# Adafruit_ATECC608.net
KiCad netlist of a schematic drawn in EAGLE
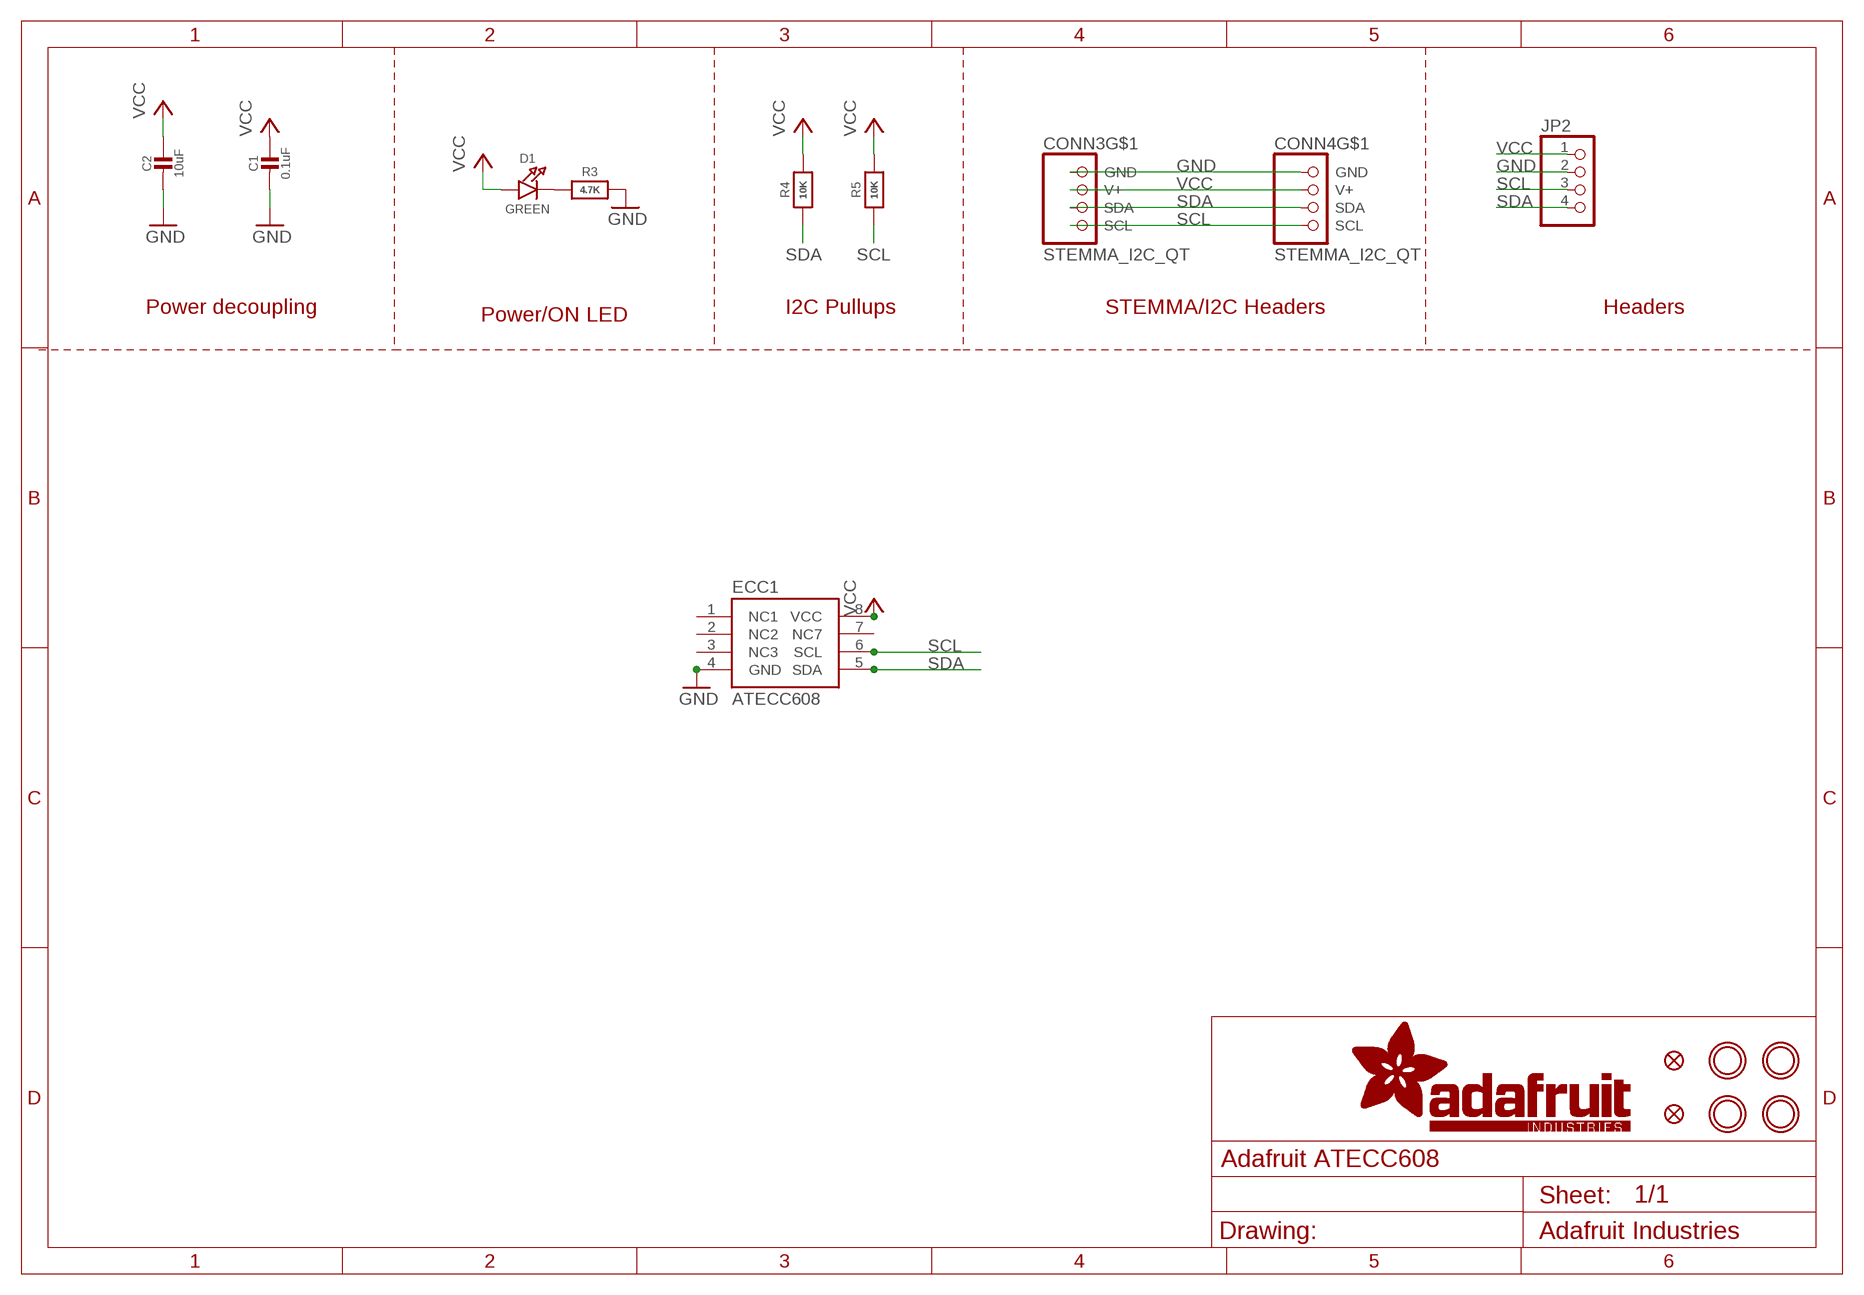
[diagram p0: schematic, sheet 1]

(export (version "E")
  (design (tool "Eeschema 10.0.6"))
  (components
    (comp (ref "C1")
      (value "0.1uF")
      (footprint "eagle-import:0603-NO")
      (libsource (lib "eagle-import") (part "CAP_CERAMIC0603_NO"))
    )
    (comp (ref "C2")
      (value "10uF")
      (footprint "eagle-import:0805-NO")
      (libsource (lib "eagle-import") (part "CAP_CERAMIC0805-NOOUTLINE"))
    )
    (comp (ref "CONN3")
      (value "STEMMA_I2C_QT")
      (footprint "eagle-import:JST_SH4")
      (libsource (lib "eagle-import") (part "STEMMA_I2C_QT"))
    )
    (comp (ref "CONN4")
      (value "STEMMA_I2C_QT")
      (footprint "eagle-import:JST_SH4")
      (libsource (lib "eagle-import") (part "STEMMA_I2C_QT"))
    )
    (comp (ref "D1")
      (value "GREEN")
      (footprint "eagle-import:CHIPLED_0603_NOOUTLINE")
      (libsource (lib "eagle-import") (part "LED0603_NOOUTLINE"))
    )
    (comp (ref "ECC1")
      (value "ATECC608")
      (footprint "eagle-import:SOIC8")
      (libsource (lib "eagle-import") (part "ATECC108"))
    )
    (comp (ref "FID3")
      (value "FIDUCIAL_1MM")
      (footprint "eagle-import:FIDUCIAL_1MM")
      (libsource (lib "eagle-import") (part "FIDUCIAL_1MM"))
    )
    (comp (ref "FID4")
      (value "FIDUCIAL_1MM")
      (footprint "eagle-import:FIDUCIAL_1MM")
      (libsource (lib "eagle-import") (part "FIDUCIAL_1MM"))
    )
    (comp (ref "JP2")
      (value "HEADER-1X4ROUND")
      (footprint "eagle-import:1X04_ROUND")
      (libsource (lib "eagle-import") (part "HEADER-1X4ROUND"))
    )
    (comp (ref "R3")
      (value "4.7K")
      (footprint "eagle-import:0603-NO")
      (libsource (lib "eagle-import") (part "RESISTOR_0603_NOOUT"))
    )
    (comp (ref "R4")
      (value "10K")
      (footprint "eagle-import:0603-NO")
      (libsource (lib "eagle-import") (part "RESISTOR_0603_NOOUT"))
    )
    (comp (ref "R5")
      (value "10K")
      (footprint "eagle-import:0603-NO")
      (libsource (lib "eagle-import") (part "RESISTOR_0603_NOOUT"))
    )
    (comp (ref "U$11")
      (value "MOUNTINGHOLE2.5")
      (footprint "eagle-import:MOUNTINGHOLE_2.5_PLATED")
      (libsource (lib "eagle-import") (part "MOUNTINGHOLE2.5"))
    )
    (comp (ref "U$12")
      (value "MOUNTINGHOLE2.5")
      (footprint "eagle-import:MOUNTINGHOLE_2.5_PLATED")
      (libsource (lib "eagle-import") (part "MOUNTINGHOLE2.5"))
    )
    (comp (ref "U$14")
      (value "MOUNTINGHOLE2.5")
      (footprint "eagle-import:MOUNTINGHOLE_2.5_PLATED")
      (libsource (lib "eagle-import") (part "MOUNTINGHOLE2.5"))
    )
    (comp (ref "U$15")
      (value "MOUNTINGHOLE2.5")
      (footprint "eagle-import:MOUNTINGHOLE_2.5_PLATED")
      (libsource (lib "eagle-import") (part "MOUNTINGHOLE2.5"))
    )
  )
  (nets
    (net (code "1") (name "/SCL") (class "Default")
      (node (ref "CONN3") (pin "4") (pinfunction "SCL_4") (pintype "passive"))
      (node (ref "CONN4") (pin "4") (pinfunction "SCL_4") (pintype "passive"))
      (node (ref "ECC1") (pin "6") (pinfunction "SCL_6") (pintype "bidirectional"))
      (node (ref "JP2") (pin "3") (pinfunction "3_3") (pintype "passive"))
      (node (ref "R5") (pin "1") (pinfunction "1_1") (pintype "passive"))
    )
    (net (code "2") (name "/SDA") (class "Default")
      (node (ref "CONN3") (pin "3") (pinfunction "SDA_3") (pintype "passive"))
      (node (ref "CONN4") (pin "3") (pinfunction "SDA_3") (pintype "passive"))
      (node (ref "ECC1") (pin "5") (pinfunction "SDA_5") (pintype "bidirectional"))
      (node (ref "JP2") (pin "4") (pinfunction "4_4") (pintype "passive"))
      (node (ref "R4") (pin "1") (pinfunction "1_1") (pintype "passive"))
    )
    (net (code "3") (name "GND") (class "Default")
      (node (ref "C1") (pin "2") (pinfunction "2_2") (pintype "passive"))
      (node (ref "C2") (pin "2") (pinfunction "2_2") (pintype "passive"))
      (node (ref "CONN3") (pin "1") (pinfunction "GND_1") (pintype "passive"))
      (node (ref "CONN4") (pin "1") (pinfunction "GND_1") (pintype "passive"))
      (node (ref "ECC1") (pin "4") (pinfunction "GND_4") (pintype "power_in"))
      (node (ref "JP2") (pin "2") (pinfunction "2_2") (pintype "passive"))
      (node (ref "R3") (pin "2") (pinfunction "2_2") (pintype "passive"))
    )
    (net (code "4") (name "Net-(D1-PadC)") (class "Default")
      (node (ref "D1") (pin "C") (pinfunction "C_C") (pintype "passive"))
      (node (ref "R3") (pin "1") (pinfunction "1_1") (pintype "passive"))
    )
    (net (code "5") (name "VCC") (class "Default")
      (node (ref "C1") (pin "1") (pinfunction "1_1") (pintype "passive"))
      (node (ref "C2") (pin "1") (pinfunction "1_1") (pintype "passive"))
      (node (ref "CONN3") (pin "2") (pinfunction "V+_2") (pintype "passive"))
      (node (ref "CONN4") (pin "2") (pinfunction "V+_2") (pintype "passive"))
      (node (ref "D1") (pin "A") (pinfunction "A_A") (pintype "passive"))
      (node (ref "ECC1") (pin "8") (pinfunction "VCC_8") (pintype "power_in"))
      (node (ref "JP2") (pin "1") (pinfunction "1_1") (pintype "passive"))
      (node (ref "R4") (pin "2") (pinfunction "2_2") (pintype "passive"))
      (node (ref "R5") (pin "2") (pinfunction "2_2") (pintype "passive"))
    )
    (net (code "6") (name "unconnected-(ECC1-NC1-Pad1)") (class "Default")
      (node (ref "ECC1") (pin "1") (pinfunction "NC1_1") (pintype "bidirectional"))
    )
    (net (code "7") (name "unconnected-(ECC1-NC2-Pad2)") (class "Default")
      (node (ref "ECC1") (pin "2") (pinfunction "NC2_2") (pintype "no_connect"))
    )
    (net (code "8") (name "unconnected-(ECC1-NC3-Pad3)") (class "Default")
      (node (ref "ECC1") (pin "3") (pinfunction "NC3_3") (pintype "no_connect"))
    )
    (net (code "9") (name "unconnected-(ECC1-NC7-Pad7)") (class "Default")
      (node (ref "ECC1") (pin "7") (pinfunction "NC7_7") (pintype "no_connect"))
    )
  )
)
